# C210_0006_Power_220601.net
KiCad netlist of a schematic drawn in Altium Designer
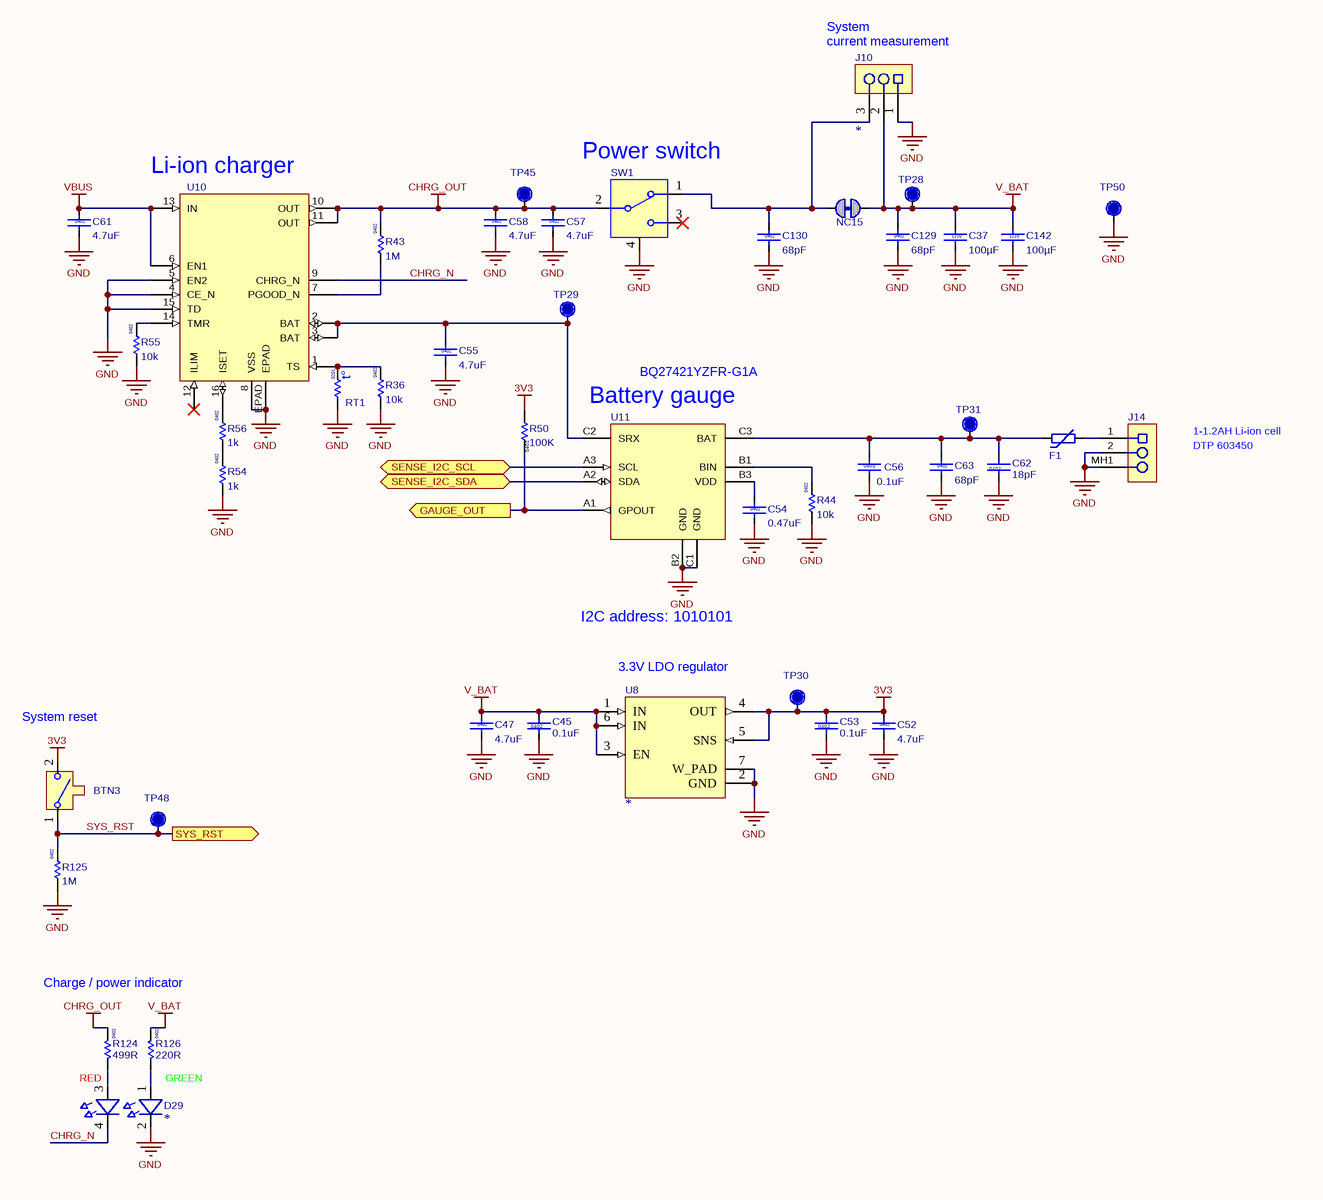
[diagram p0: C210_0006_Power_220601.SchDoc]

(export (version "E")
  (design (tool "Eeschema 10.0.6"))
  (components
    (comp (ref "BTN3")
      (value "135-00006")
      (footprint "B3U-3000P")
      (description "Button SPST-NO Off-MOM, 50mA 12V, Right Angle, SMT")
      (fields (field (name "VOLTAGE") "12VDC"))
      (libsource (lib "Arena_Parts_DB_Lib") (part "SW_SPST"))
    )
    (comp (ref "C37")
      (value "100µF")
      (footprint "Cap 1210")
      (description "100µF ±20% 10V Ceramic Capacitor X5R 1210 (3225 Metric)")
      (fields
        (field (name "SIZE") "1210")
        (field (name "PART NUMBER") "120-00223")
        (field (name "TOLERANCE") "+/- 20%")
      )
      (libsource (lib "Arena_Parts_DB_Lib") (part "Cap Chip"))
    )
    (comp (ref "C45")
      (value "0.1uF")
      (footprint "Cap 0402 HD")
      (description "Cap, Ceramic 0.1uF 10V 10% X5R 0402")
      (fields
        (field (name "SIZE") "0402")
        (field (name "PART NUMBER") "120-00016")
        (field (name "MANUFACTURER") "Murata Electronics North America")
      )
      (libsource (lib "Arena_Parts_DB_Lib") (part "Cap Chip"))
    )
    (comp (ref "C47")
      (value "4.7uF")
      (footprint "Cap 0402 HD")
      (description "Cap, Ceramic 4.7uF 10V 20% X5R 0402")
      (fields
        (field (name "SIZE") "0402")
        (field (name "PART NUMBER") "120-00020")
        (field (name "TOLERANCE") "+/- 20%")
      )
      (libsource (lib "Arena_Parts_DB_Lib") (part "Cap Chip"))
    )
    (comp (ref "C52")
      (value "4.7uF")
      (footprint "Cap 0402 HD")
      (description "Cap, Ceramic 4.7uF 10V 20% X5R 0402")
      (fields
        (field (name "SIZE") "0402")
        (field (name "PART NUMBER") "120-00020")
        (field (name "TOLERANCE") "+/- 20%")
      )
      (libsource (lib "Arena_Parts_DB_Lib") (part "Cap Chip"))
    )
    (comp (ref "C53")
      (value "0.1uF")
      (footprint "Cap 0402 HD")
      (description "Cap, Ceramic 0.1uF 10V 10% X5R 0402")
      (fields
        (field (name "SIZE") "0402")
        (field (name "PART NUMBER") "120-00016")
        (field (name "MANUFACTURER") "Murata Electronics North America")
      )
      (libsource (lib "Arena_Parts_DB_Lib") (part "Cap Chip"))
    )
    (comp (ref "C54")
      (value "0.47uF")
      (footprint "Cap 0402 HD")
      (description "Cap, Ceramic, 0.47UF 10V 10% X5R 0402")
      (fields
        (field (name "SIZE") "0402")
        (field (name "PART NUMBER") "120-00072")
        (field (name "TOLERANCE") "+/- 10%")
      )
      (libsource (lib "Arena_Parts_DB_Lib") (part "Cap Chip"))
    )
    (comp (ref "C55")
      (value "4.7uF")
      (footprint "Cap 0402 HD")
      (description "Cap, Ceramic 4.7uF 10V 20% X5R 0402")
      (fields
        (field (name "SIZE") "0402")
        (field (name "PART NUMBER") "120-00020")
        (field (name "TOLERANCE") "+/- 20%")
      )
      (libsource (lib "Arena_Parts_DB_Lib") (part "Cap Chip"))
    )
    (comp (ref "C56")
      (value "0.1uF")
      (footprint "Cap 0402 HD")
      (description "Cap, Ceramic 0.1uF 10V 10% X5R 0402")
      (fields
        (field (name "SIZE") "0402")
        (field (name "PART NUMBER") "120-00016")
        (field (name "MANUFACTURER") "Murata Electronics North America")
      )
      (libsource (lib "Arena_Parts_DB_Lib") (part "Cap Chip"))
    )
    (comp (ref "C57")
      (value "4.7uF")
      (footprint "Cap 0402 HD")
      (description "Cap, Ceramic 4.7uF 10V 20% X5R 0402")
      (fields
        (field (name "SIZE") "0402")
        (field (name "PART NUMBER") "120-00020")
        (field (name "TOLERANCE") "+/- 20%")
      )
      (libsource (lib "Arena_Parts_DB_Lib") (part "Cap Chip"))
    )
    (comp (ref "C58")
      (value "4.7uF")
      (footprint "Cap 0402 HD")
      (description "Cap, Ceramic 4.7uF 10V 20% X5R 0402")
      (fields
        (field (name "SIZE") "0402")
        (field (name "PART NUMBER") "120-00020")
        (field (name "TOLERANCE") "+/- 20%")
      )
      (libsource (lib "Arena_Parts_DB_Lib") (part "Cap Chip"))
    )
    (comp (ref "C61")
      (value "4.7uF")
      (footprint "Cap 0402 HD")
      (description "Cap, Ceramic 4.7uF 10V 20% X5R 0402")
      (fields
        (field (name "SIZE") "0402")
        (field (name "PART NUMBER") "120-00020")
        (field (name "TOLERANCE") "+/- 20%")
      )
      (libsource (lib "Arena_Parts_DB_Lib") (part "Cap Chip"))
    )
    (comp (ref "C62")
      (value "18pF")
      (footprint "Cap 0402 HD")
      (description "Cap, Ceramic 18pF 50V 5% NP0 0402")
      (fields
        (field (name "SIZE") "0402")
        (field (name "PART NUMBER") "120-00041")
        (field (name "TOLERANCE") "+/- 5%")
      )
      (libsource (lib "Arena_Parts_DB_Lib") (part "Cap Chip"))
    )
    (comp (ref "C63")
      (value "68pF")
      (footprint "Cap 0402 HD")
      (description "Cap, Ceramic, 68pF, 50V, 1%, NP0, 0402")
      (fields
        (field (name "SIZE") "0402")
        (field (name "PART NUMBER") "120-00047")
        (field (name "TOLERANCE") "+/- 1%")
      )
      (libsource (lib "Arena_Parts_DB_Lib") (part "Cap Chip"))
    )
    (comp (ref "C129")
      (value "68pF")
      (footprint "Cap 0402 HD")
      (description "Cap, Ceramic, 68pF, 50V, 1%, NP0, 0402")
      (fields
        (field (name "SIZE") "0402")
        (field (name "PART NUMBER") "120-00047")
        (field (name "TOLERANCE") "+/- 1%")
      )
      (libsource (lib "Arena_Parts_DB_Lib") (part "Cap Chip"))
    )
    (comp (ref "C130")
      (value "68pF")
      (footprint "Cap 0402 HD")
      (description "Cap, Ceramic, 68pF, 50V, 1%, NP0, 0402")
      (fields
        (field (name "SIZE") "0402")
        (field (name "PART NUMBER") "120-00047")
        (field (name "TOLERANCE") "+/- 1%")
      )
      (libsource (lib "Arena_Parts_DB_Lib") (part "Cap Chip"))
    )
    (comp (ref "C142")
      (value "100µF")
      (footprint "Cap 1210")
      (description "100µF ±20% 10V Ceramic Capacitor X5R 1210 (3225 Metric)")
      (fields
        (field (name "SIZE") "1210")
        (field (name "PART NUMBER") "120-00223")
        (field (name "TOLERANCE") "+/- 20%")
      )
      (libsource (lib "Arena_Parts_DB_Lib") (part "Cap Chip"))
    )
    (comp (ref "D29")
      (value "115-00013")
      (footprint "LED_4Pin_4213_RA_3215")
      (description "Dual LED, Red/Green, Right Angle, Dome 1208")
      (fields (field (name "COLOR") "*") (field (name "VOLTAGE") "None"))
      (libsource (lib "Arena_Parts_DB_Lib") (part "LED_Dual_1"))
    )
    (comp (ref "F1")
      (value "190-00005")
      (footprint "Fuse 1206")
      (description "Fuse, PTC 8V, 750mA, hold, 1.5A trip, 1206")
      (fields (field (name "VOLTAGE") "None"))
      (libsource (lib "Arena_Parts_DB_Lib") (part "PTC_Fuse"))
    )
    (comp (ref "J10")
      (value "130-00105")
      (footprint "HDR-0.1P-3Pin-1Row-SMT")
      (description "Header, 0.100\" Pitch, 3 Pin, Vertical SMT, Black")
      (fields (field (name "MANUFACTURER P/N") "*") (field (name "VOLTAGE") "None"))
      (libsource (lib "Arena_Parts_DB_Lib") (part "CON-3Pin_1Row"))
    )
    (comp (ref "J14")
      (value "S2B-PH-SM4-TB")
      (footprint "S2B-PH-SM4-TB")
      (description "Conn, SMT, 0.079\" Pitch, 2 Pin, R/A, Black")
      (fields (field (name "VOLTAGE") "None"))
      (libsource (lib "S2B-PH-SM4-TB") (part "S2B-PH-SM4-TB"))
    )
    (comp (ref "NC15")
      (value "Solderbridge-ShortDNP")
      (footprint "Solderbridge-Short")
      (description "Solderbridge-Short")
      (fields (field (name "ADDED BY") "Paul B"))
      (libsource (lib "PCB_Misc") (part "Solderbridge-Short"))
    )
    (comp (ref "R36")
      (value "10k")
      (footprint "RES 0402 HD")
      (description "Resistor 10k ohm 1% 1/16W, 0402")
      (fields
        (field (name "SIZE") "0402")
        (field (name "PART NUMBER") "180-00024")
        (field (name "POWER") "1/16W")
      )
      (libsource (lib "Arena_Parts_DB_Lib") (part "Res sm"))
    )
    (comp (ref "R43")
      (value "1M")
      (footprint "RES 0402 HD")
      (description "Resistor 1M ohm 1%, 1/16W, 0402")
      (fields
        (field (name "SIZE") "0402")
        (field (name "PART NUMBER") "180-00054")
        (field (name "POWER") "1/16W")
      )
      (libsource (lib "Arena_Parts_DB_Lib") (part "Res sm"))
    )
    (comp (ref "R44")
      (value "10k")
      (footprint "RES 0402 HD")
      (description "Resistor 10k ohm 1% 1/16W, 0402")
      (fields
        (field (name "SIZE") "0402")
        (field (name "PART NUMBER") "180-00024")
        (field (name "POWER") "1/16W")
      )
      (libsource (lib "Arena_Parts_DB_Lib") (part "Res sm"))
    )
    (comp (ref "R50")
      (value "100K")
      (footprint "RES 0402 HD")
      (description "Resistor 100K ohm 1% 1/16W, 0402")
      (fields
        (field (name "SIZE") "0402")
        (field (name "PART NUMBER") "180-00093")
        (field (name "POWER") "1/16W")
      )
      (libsource (lib "Arena_Parts_DB_Lib") (part "Res sm"))
    )
    (comp (ref "R54")
      (value "1k")
      (footprint "RES 0402 HD")
      (description "Resistor 1k ohm 1% 1/16W, 0402")
      (fields
        (field (name "SIZE") "0402")
        (field (name "PART NUMBER") "180-00021")
        (field (name "POWER") "1/16W")
      )
      (libsource (lib "Arena_Parts_DB_Lib") (part "Res sm"))
    )
    (comp (ref "R55")
      (value "10k")
      (footprint "RES 0402 HD")
      (description "Resistor 10k ohm 1% 1/16W, 0402")
      (fields
        (field (name "SIZE") "0402")
        (field (name "PART NUMBER") "180-00024")
        (field (name "POWER") "1/16W")
      )
      (libsource (lib "Arena_Parts_DB_Lib") (part "Res sm"))
    )
    (comp (ref "R56")
      (value "1k")
      (footprint "RES 0402 HD")
      (description "Resistor 1k ohm 1% 1/16W, 0402")
      (fields
        (field (name "SIZE") "0402")
        (field (name "PART NUMBER") "180-00021")
        (field (name "POWER") "1/16W")
      )
      (libsource (lib "Arena_Parts_DB_Lib") (part "Res sm"))
    )
    (comp (ref "R124")
      (value "499R")
      (footprint "RES 0402 HD")
      (description "Resistor, 499ohm, 1%, 1/16W, 0402")
      (fields
        (field (name "SIZE") "0402")
        (field (name "PART NUMBER") "180-00031")
        (field (name "MANUFACTURER") "Rohm Semiconductor")
      )
      (libsource (lib "Arena_Parts_DB_Lib") (part "Res sm"))
    )
    (comp (ref "R125")
      (value "1M")
      (footprint "RES 0402 HD")
      (description "Resistor 1M ohm 1%, 1/16W, 0402")
      (fields
        (field (name "SIZE") "0402")
        (field (name "PART NUMBER") "180-00054")
        (field (name "POWER") "1/16W")
      )
      (libsource (lib "Arena_Parts_DB_Lib") (part "Res sm"))
    )
    (comp (ref "R126")
      (value "220R")
      (footprint "RES 0402 HD")
      (description "Resistor, 220ohm, 5%, 1/16W, 0402.")
      (fields
        (field (name "SIZE") "0402")
        (field (name "PART NUMBER") "180-00098")
        (field (name "MANUFACTURER") "Panasonic Electronic Components")
      )
      (libsource (lib "Arena_Parts_DB_Lib") (part "Res sm"))
    )
    (comp (ref "RT1")
      (value "Res Thermal")
      (footprint "RES 0201 HD")
      (description "Thermistor, 10Kohm, NTC 5%, 0201, 0.6mm x 0.3mm")
      (fields
        (field (name "SIZE") "0201")
        (field (name "PART NUMBER") "182-00002")
        (field (name "POWER") "1/20W")
      )
      (libsource (lib "Arena_Parts_DB_Lib") (part "Res Thermal"))
    )
    (comp (ref "SW1")
      (value "137-00002")
      (footprint "EG1224")
      (description "Slide switch, SPDT, 3 Pin, 500mA, 15V, Through Hole")
      (fields (field (name "VOLTAGE") "15V"))
      (libsource (lib "Arena_Parts_DB_Lib") (part "SW_SPDT_Shield"))
    )
    (comp (ref "TP28")
      (value "TP")
      (footprint "TP12R")
      (description "Testpoint, Round 1.0mm Dia")
      (fields
        (field (name "PART NUMBER") "TP10R")
        (field (name "ADDED BY") "Jeremy D")
        (field (name "CHECKED BY") "Paul B")
      )
      (libsource (lib "PCB_Misc") (part "TP_R"))
    )
    (comp (ref "TP29")
      (value "TP")
      (footprint "TP12R")
      (description "Testpoint, Round 1.0mm Dia")
      (fields
        (field (name "PART NUMBER") "TP10R")
        (field (name "ADDED BY") "Jeremy D")
        (field (name "CHECKED BY") "Paul B")
      )
      (libsource (lib "PCB_Misc") (part "TP_R"))
    )
    (comp (ref "TP30")
      (value "TP")
      (footprint "TP12R")
      (description "Testpoint, Round 1.0mm Dia")
      (fields
        (field (name "PART NUMBER") "TP10R")
        (field (name "ADDED BY") "Jeremy D")
        (field (name "CHECKED BY") "Paul B")
      )
      (libsource (lib "PCB_Misc") (part "TP_R"))
    )
    (comp (ref "TP31")
      (value "TP")
      (footprint "TP12R")
      (description "Testpoint, Round 1.0mm Dia")
      (fields
        (field (name "PART NUMBER") "TP10R")
        (field (name "ADDED BY") "Jeremy D")
        (field (name "CHECKED BY") "Paul B")
      )
      (libsource (lib "PCB_Misc") (part "TP_R"))
    )
    (comp (ref "TP45")
      (value "TP")
      (footprint "TP12R")
      (description "Testpoint, Round 1.0mm Dia")
      (fields
        (field (name "PART NUMBER") "TP10R")
        (field (name "ADDED BY") "Jeremy D")
        (field (name "CHECKED BY") "Paul B")
      )
      (libsource (lib "PCB_Misc") (part "TP_R"))
    )
    (comp (ref "TP48")
      (value "TP")
      (footprint "TP12R")
      (description "Testpoint, Round 1.0mm Dia")
      (fields
        (field (name "PART NUMBER") "TP10R")
        (field (name "ADDED BY") "Jeremy D")
        (field (name "CHECKED BY") "Paul B")
      )
      (libsource (lib "PCB_Misc") (part "TP_R"))
    )
    (comp (ref "TP50")
      (value "TP")
      (footprint "TP12R")
      (description "Testpoint, Round 1.0mm Dia")
      (fields
        (field (name "PART NUMBER") "TP10R")
        (field (name "ADDED BY") "Jeremy D")
        (field (name "CHECKED BY") "Paul B")
      )
      (libsource (lib "PCB_Misc") (part "TP_R"))
    )
    (comp (ref "U8")
      (value "260-00045")
      (footprint "DFN0.95P-6Pin_W-Pad")
      (description "IC REG LDO 3.3V 1A 6DFN")
      (fields (field (name "MANUFACTURER P/N") "*") (field (name "VOLTAGE") "3.3V"))
      (libsource (lib "Arena_Parts_DB_Lib") (part "NCP692MN33T2G"))
    )
    (comp (ref "U10")
      (value "bq24230")
      (footprint "QFN0.5P3x3-16Pin_W-Pad")
      (description "BAT CHARGER, Li-ION, SMT, USB, PWR PATH, 500mA, 4.4V, 3mmx3mm QFN-16")
      (fields (field (name "VOLTAGE") "5-6.5V"))
      (libsource (lib "bq24230") (part "bq24230"))
    )
    (comp (ref "U11")
      (value "BQ27421")
      (footprint "BQ27421")
      (description "IC, SMT, BATTERY GAUGE, INGLE CELL Li-ION, COULOMB COUNTER, DSBGA-9 1.6mmX1.6mm")
      (libsource (lib "BQ27421") (part "BQ27421"))
    )
  )
  (nets
    (net (code "1") (name "/CHRG_N") (class "Default")
      (node (ref "D29") (pin "4") (pinfunction "C2_4") (pintype "passive"))
      (node (ref "U10") (pin "9") (pinfunction "CHRG_N_9") (pintype "open_collector"))
    )
    (net (code "2") (name "/GAUGE_OUT") (class "Default")
      (node (ref "R50") (pin "2") (pinfunction "2_2") (pintype "passive"))
      (node (ref "U11") (pin "A1") (pinfunction "GPOUT_A1") (pintype "output"))
    )
    (net (code "3") (name "/SENSE_I2C_SCL") (class "Default")
      (node (ref "U11") (pin "A3") (pinfunction "SCL_A3") (pintype "input"))
    )
    (net (code "4") (name "/SENSE_I2C_SDA") (class "Default")
      (node (ref "U11") (pin "A2") (pinfunction "SDA_A2") (pintype "bidirectional"))
    )
    (net (code "5") (name "/SYS_RST") (class "Default")
      (node (ref "BTN3") (pin "1") (pinfunction "1_1") (pintype "passive"))
      (node (ref "R125") (pin "2") (pinfunction "2_2") (pintype "passive"))
      (node (ref "TP48") (pin "1") (pintype "passive"))
    )
    (net (code "6") (name "3V3") (class "Default")
      (node (ref "BTN3") (pin "2") (pinfunction "2_2") (pintype "passive"))
      (node (ref "C52") (pin "1") (pinfunction "1_1") (pintype "passive"))
      (node (ref "C53") (pin "2") (pinfunction "2_2") (pintype "passive"))
      (node (ref "R50") (pin "1") (pinfunction "1_1") (pintype "passive"))
      (node (ref "TP30") (pin "1") (pintype "passive"))
      (node (ref "U8") (pin "4") (pinfunction "OUT_4") (pintype "output"))
      (node (ref "U8") (pin "5") (pinfunction "SNS_5") (pintype "input"))
    )
    (net (code "7") (name "CHRG_OUT") (class "Default")
      (node (ref "C57") (pin "1") (pinfunction "1_1") (pintype "passive"))
      (node (ref "C58") (pin "1") (pinfunction "1_1") (pintype "passive"))
      (node (ref "R124") (pin "2") (pinfunction "2_2") (pintype "passive"))
      (node (ref "R43") (pin "2") (pinfunction "2_2") (pintype "passive"))
      (node (ref "SW1") (pin "2") (pinfunction "2_2") (pintype "passive"))
      (node (ref "TP45") (pin "1") (pintype "passive"))
      (node (ref "U10") (pin "10") (pinfunction "OUT_10") (pintype "output"))
      (node (ref "U10") (pin "11") (pinfunction "OUT_11") (pintype "output"))
    )
    (net (code "8") (name "GND") (class "Default")
      (node (ref "C129") (pin "2") (pinfunction "2_2") (pintype "passive"))
      (node (ref "C130") (pin "2") (pinfunction "2_2") (pintype "passive"))
      (node (ref "C142") (pin "2") (pinfunction "2_2") (pintype "passive"))
      (node (ref "C37") (pin "2") (pinfunction "2_2") (pintype "passive"))
      (node (ref "C45") (pin "1") (pinfunction "1_1") (pintype "passive"))
      (node (ref "C47") (pin "2") (pinfunction "2_2") (pintype "passive"))
      (node (ref "C52") (pin "2") (pinfunction "2_2") (pintype "passive"))
      (node (ref "C53") (pin "1") (pinfunction "1_1") (pintype "passive"))
      (node (ref "C54") (pin "2") (pinfunction "2_2") (pintype "passive"))
      (node (ref "C55") (pin "2") (pinfunction "2_2") (pintype "passive"))
      (node (ref "C56") (pin "1") (pinfunction "1_1") (pintype "passive"))
      (node (ref "C57") (pin "2") (pinfunction "2_2") (pintype "passive"))
      (node (ref "C58") (pin "2") (pinfunction "2_2") (pintype "passive"))
      (node (ref "C61") (pin "2") (pinfunction "2_2") (pintype "passive"))
      (node (ref "C62") (pin "1") (pinfunction "1_1") (pintype "passive"))
      (node (ref "C63") (pin "2") (pinfunction "2_2") (pintype "passive"))
      (node (ref "D29") (pin "2") (pinfunction "C1_2") (pintype "passive"))
      (node (ref "J10") (pin "1") (pinfunction "1_1") (pintype "passive"))
      (node (ref "J14") (pin "2") (pinfunction "2_2") (pintype "passive"))
      (node (ref "J14") (pin "MH1") (pinfunction "MH1_MH1") (pintype "passive"))
      (node (ref "R125") (pin "1") (pinfunction "1_1") (pintype "passive"))
      (node (ref "R36") (pin "1") (pinfunction "1_1") (pintype "passive"))
      (node (ref "R44") (pin "1") (pinfunction "1_1") (pintype "passive"))
      (node (ref "R54") (pin "1") (pinfunction "1_1") (pintype "passive"))
      (node (ref "R55") (pin "1") (pinfunction "1_1") (pintype "passive"))
      (node (ref "RT1") (pin "2") (pinfunction "2_2") (pintype "passive"))
      (node (ref "SW1") (pin "4") (pinfunction "GND_4") (pintype "power_in"))
      (node (ref "TP50") (pin "1") (pintype "passive"))
      (node (ref "U10") (pin "15") (pinfunction "TD_15") (pintype "input"))
      (node (ref "U10") (pin "4") (pinfunction "CE_N_4") (pintype "input"))
      (node (ref "U10") (pin "5") (pinfunction "EN2_5") (pintype "input"))
      (node (ref "U10") (pin "8") (pinfunction "VSS_8") (pintype "power_in"))
      (node (ref "U10") (pin "EPAD") (pinfunction "EPAD_EPAD") (pintype "power_in"))
      (node (ref "U11") (pin "B2") (pinfunction "GND_B2") (pintype "power_in"))
      (node (ref "U11") (pin "C1") (pinfunction "GND_C1") (pintype "power_in"))
      (node (ref "U8") (pin "2") (pinfunction "GND_2") (pintype "power_in"))
      (node (ref "U8") (pin "7") (pinfunction "W_PAD_7") (pintype "power_in"))
    )
    (net (code "9") (name "Net-(C130-Pad1)") (class "Default")
      (node (ref "C130") (pin "1") (pinfunction "1_1") (pintype "passive"))
      (node (ref "J10") (pin "3") (pinfunction "3_3") (pintype "passive"))
      (node (ref "NC15") (pin "2") (pinfunction "2_2") (pintype "passive"))
      (node (ref "SW1") (pin "1") (pinfunction "1_1") (pintype "passive"))
    )
    (net (code "10") (name "Net-(D29-A1)") (class "Default")
      (node (ref "D29") (pin "1") (pinfunction "A1_1") (pintype "passive"))
      (node (ref "R126") (pin "1") (pinfunction "1_1") (pintype "passive"))
    )
    (net (code "11") (name "Net-(D29-A2)") (class "Default")
      (node (ref "D29") (pin "3") (pinfunction "A2_3") (pintype "passive"))
      (node (ref "R124") (pin "1") (pinfunction "1_1") (pintype "passive"))
    )
    (net (code "12") (name "Net-(F1-Pad2)") (class "Default")
      (node (ref "F1") (pin "2") (pinfunction "2_2") (pintype "passive"))
      (node (ref "J14") (pin "1") (pinfunction "1_1") (pintype "passive"))
    )
    (net (code "13") (name "Net-(R54-Pad2)") (class "Default")
      (node (ref "R54") (pin "2") (pinfunction "2_2") (pintype "passive"))
      (node (ref "R56") (pin "1") (pinfunction "1_1") (pintype "passive"))
    )
    (net (code "14") (name "Net-(U10-ISET)") (class "Default")
      (node (ref "R56") (pin "2") (pinfunction "2_2") (pintype "passive"))
      (node (ref "U10") (pin "16") (pinfunction "ISET_16") (pintype "bidirectional"))
    )
    (net (code "15") (name "Net-(U10-PGOOD_N)") (class "Default")
      (node (ref "R43") (pin "1") (pinfunction "1_1") (pintype "passive"))
      (node (ref "U10") (pin "7") (pinfunction "PGOOD_N_7") (pintype "open_collector"))
    )
    (net (code "16") (name "Net-(U10-TMR)") (class "Default")
      (node (ref "R55") (pin "2") (pinfunction "2_2") (pintype "passive"))
      (node (ref "U10") (pin "14") (pinfunction "TMR_14") (pintype "input"))
    )
    (net (code "17") (name "Net-(U10-TS)") (class "Default")
      (node (ref "R36") (pin "2") (pinfunction "2_2") (pintype "passive"))
      (node (ref "RT1") (pin "1") (pinfunction "1_1") (pintype "passive"))
      (node (ref "U10") (pin "1") (pinfunction "TS_1") (pintype "input"))
    )
    (net (code "18") (name "Net-(U11-BAT)") (class "Default")
      (node (ref "C56") (pin "2") (pinfunction "2_2") (pintype "passive"))
      (node (ref "C62") (pin "2") (pinfunction "2_2") (pintype "passive"))
      (node (ref "C63") (pin "1") (pinfunction "1_1") (pintype "passive"))
      (node (ref "F1") (pin "1") (pinfunction "1_1") (pintype "passive"))
      (node (ref "TP31") (pin "1") (pintype "passive"))
      (node (ref "U11") (pin "C3") (pinfunction "BAT_C3") (pintype "power_in"))
    )
    (net (code "19") (name "Net-(U11-BIN)") (class "Default")
      (node (ref "R44") (pin "2") (pinfunction "2_2") (pintype "passive"))
      (node (ref "U11") (pin "B1") (pinfunction "BIN_B1") (pintype "power_in"))
    )
    (net (code "20") (name "Net-(U11-SRX)") (class "Default")
      (node (ref "C55") (pin "1") (pinfunction "1_1") (pintype "passive"))
      (node (ref "TP29") (pin "1") (pintype "passive"))
      (node (ref "U10") (pin "2") (pinfunction "BAT_2") (pintype "bidirectional"))
      (node (ref "U10") (pin "3") (pinfunction "BAT_3") (pintype "bidirectional"))
      (node (ref "U11") (pin "C2") (pinfunction "SRX_C2") (pintype "passive"))
    )
    (net (code "21") (name "Net-(U11-VDD)") (class "Default")
      (node (ref "C54") (pin "1") (pinfunction "1_1") (pintype "passive"))
      (node (ref "U11") (pin "B3") (pinfunction "VDD_B3") (pintype "power_in"))
    )
    (net (code "22") (name "VBUS") (class "Default")
      (node (ref "C61") (pin "1") (pinfunction "1_1") (pintype "passive"))
      (node (ref "U10") (pin "13") (pinfunction "IN_13") (pintype "input"))
      (node (ref "U10") (pin "6") (pinfunction "EN1_6") (pintype "input"))
    )
    (net (code "23") (name "V_BAT") (class "Default")
      (node (ref "C129") (pin "1") (pinfunction "1_1") (pintype "passive"))
      (node (ref "C142") (pin "1") (pinfunction "1_1") (pintype "passive"))
      (node (ref "C37") (pin "1") (pinfunction "1_1") (pintype "passive"))
      (node (ref "C45") (pin "2") (pinfunction "2_2") (pintype "passive"))
      (node (ref "C47") (pin "1") (pinfunction "1_1") (pintype "passive"))
      (node (ref "J10") (pin "2") (pinfunction "2_2") (pintype "passive"))
      (node (ref "NC15") (pin "1") (pinfunction "1_1") (pintype "passive"))
      (node (ref "R126") (pin "2") (pinfunction "2_2") (pintype "passive"))
      (node (ref "TP28") (pin "1") (pintype "passive"))
      (node (ref "U8") (pin "1") (pinfunction "IN_1") (pintype "input"))
      (node (ref "U8") (pin "3") (pinfunction "EN_3") (pintype "input"))
      (node (ref "U8") (pin "6") (pinfunction "IN_6") (pintype "input"))
    )
    (net (code "24") (name "unconnected-(SW1-Pad3)") (class "Default")
      (node (ref "SW1") (pin "3") (pinfunction "3_3") (pintype "passive+no_connect"))
    )
    (net (code "25") (name "unconnected-(U10-ILIM-Pad12)") (class "Default")
      (node (ref "U10") (pin "12") (pinfunction "ILIM_12") (pintype "input+no_connect"))
    )
  )
)
